# Voltage_Regulators_78xx_Figure_1.net
KiCad netlist of a schematic drawn in Altium Designer
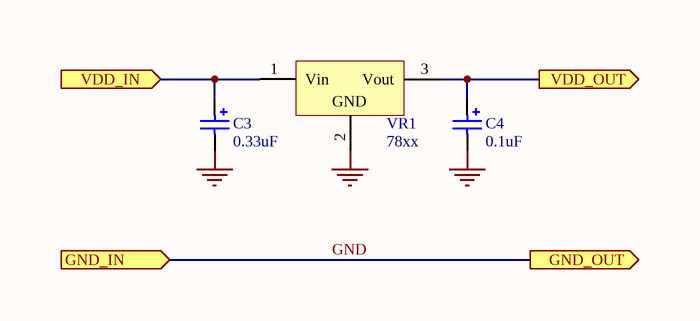
[diagram p0: Voltage_Regulators_78xx_Figure 1.SchDoc]

(export (version "E")
  (design (tool "Eeschema 10.0.6"))
  (components
    (comp (ref "C3")
      (value "0.33uF")
      (footprint "CAPPR2.5-6.3x5")
      (description "Polarized Capacitor (Radial)")
      (fields
        (field (name "MANUFACTURER") "Generic Components")
        (field (name "Comment") "Cap Pol1")
        (field (name "PUBLISHER") "Altium Limited")
      )
      (libsource (lib "Miscellaneous Devices") (part "Cap Pol1"))
    )
    (comp (ref "C4")
      (value "0.1uF")
      (footprint "CAPPR2.5-6.3x5")
      (description "Polarized Capacitor (Radial)")
      (fields
        (field (name "MANUFACTURER") "Generic Components")
        (field (name "Comment") "Cap Pol1")
        (field (name "PUBLISHER") "Altium Limited")
      )
      (libsource (lib "Miscellaneous Devices") (part "Cap Pol1"))
    )
    (comp (ref "VR1")
      (value "78xx")
      (footprint "TO257H")
      (description "Voltage Regulator")
      (fields
        (field (name "MANUFACTURER") "Generic Components")
        (field (name "Comment") "Volt Reg")
        (field (name "PUBLISHER") "Altium Limited")
      )
      (libsource (lib "Miscellaneous Devices") (part "Volt Reg"))
    )
  )
  (nets
    (net (code "1") (name "/VDD_IN") (class "Default")
      (node (ref "C3") (pin "1") (pinfunction "1_1") (pintype "passive"))
      (node (ref "VR1") (pin "1") (pinfunction "Vin_1") (pintype "passive"))
    )
    (net (code "2") (name "/VDD_OUT") (class "Default")
      (node (ref "C4") (pin "1") (pinfunction "1_1") (pintype "passive"))
      (node (ref "VR1") (pin "3") (pinfunction "Vout_3") (pintype "passive"))
    )
    (net (code "3") (name "GND") (class "Default")
      (node (ref "C3") (pin "2") (pinfunction "2_2") (pintype "passive"))
      (node (ref "C4") (pin "2") (pinfunction "2_2") (pintype "passive"))
      (node (ref "VR1") (pin "2") (pinfunction "GND_2") (pintype "passive"))
    )
  )
)
